# WEMOS_ESP8266_AktorShield.net
KiCad netlist of a schematic drawn in EAGLE
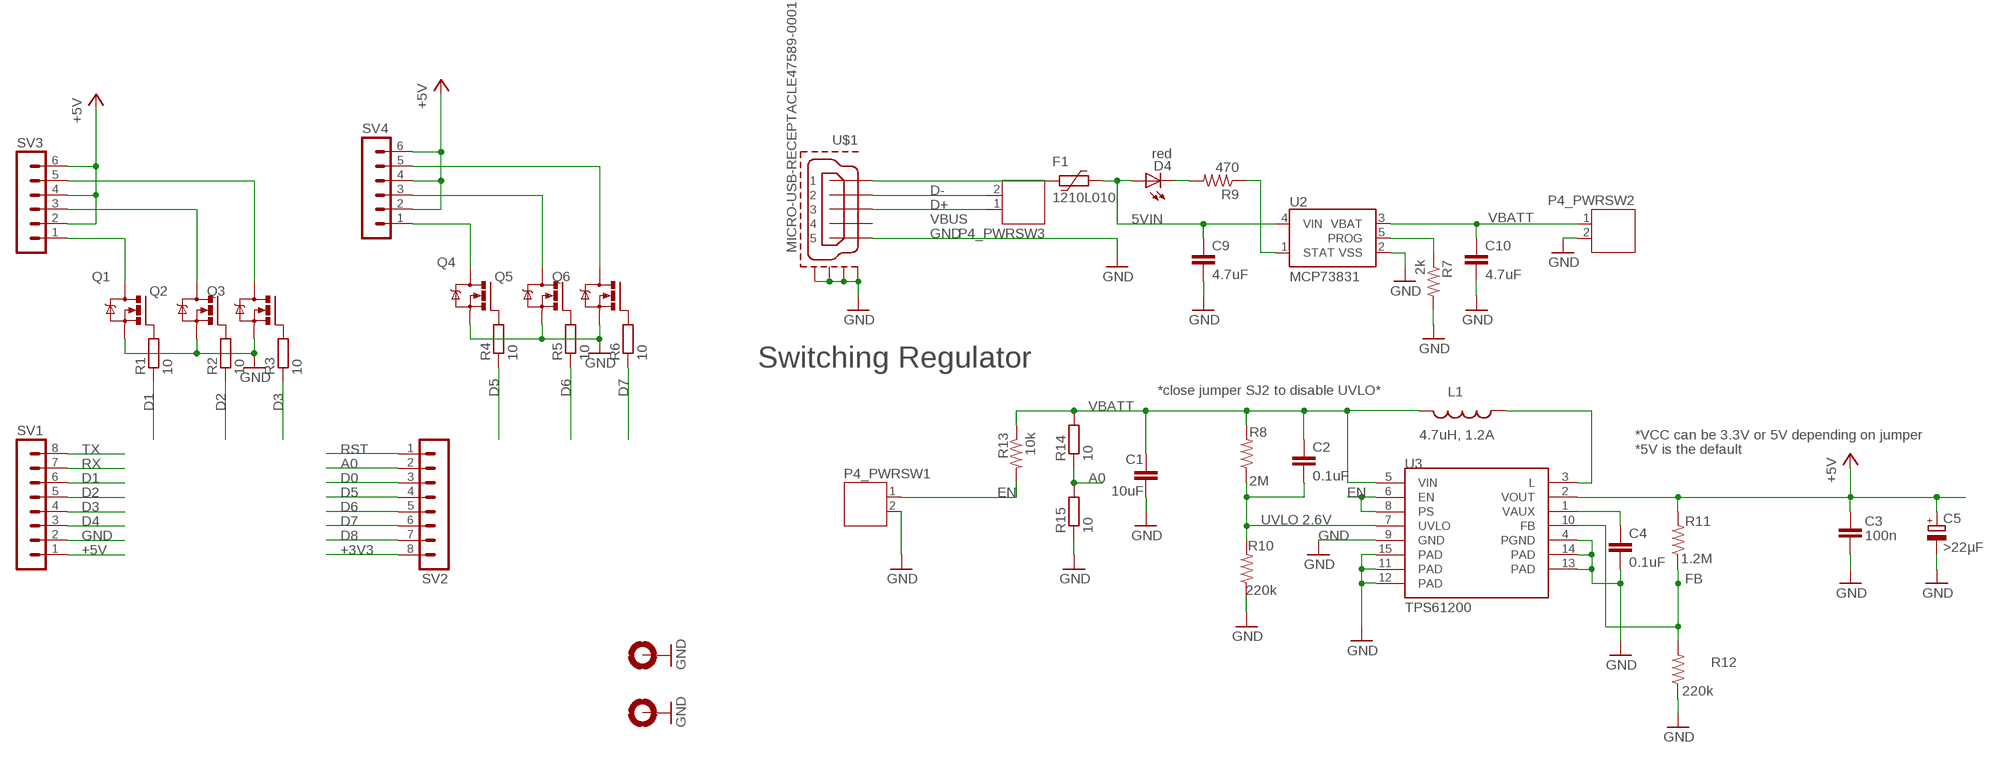
[diagram p0: schematic, sheet 1]

(export (version "E")
  (design (tool "Eeschema 10.0.6"))
  (components
    (comp (ref "C1")
      (value "10uF")
      (footprint "eagle-import:1206")
      (fields (field (name "MF") "KEMET") (field (name "MPN") "C1206C106K8RACTU"))
      (libsource (lib "eagle-import") (part "CAP1206"))
    )
    (comp (ref "C2")
      (value "0.1uF")
      (footprint "eagle-import:0603-CAP")
      (fields (field (name "MF") "YAGEO (PHYCOMP)") (field (name "MPN") "CC0603MRY5V9BB104"))
      (libsource (lib "eagle-import") (part "CAP0603-CAP"))
    )
    (comp (ref "C3")
      (value "100n")
      (footprint "eagle-import:0805")
      (fields (field (name "MF") "YAGEO (PHYCOMP)") (field (name "MPN") "CC0603MRY5V9BB104"))
      (libsource (lib "eagle-import") (part "CAP0805"))
    )
    (comp (ref "C4")
      (value "0.1uF")
      (footprint "eagle-import:0603-CAP")
      (fields (field (name "MF") "YAGEO (PHYCOMP)") (field (name "MPN") "CC0603MRY5V9BB104"))
      (libsource (lib "eagle-import") (part "CAP0603-CAP"))
    )
    (comp (ref "C5")
      (value ">22µF")
      (footprint "eagle-import:SMC_C")
      (libsource (lib "eagle-import") (part "CPOL-EUSMCC"))
    )
    (comp (ref "C9")
      (value "4.7uF")
      (footprint "eagle-import:0603-CAP")
      (fields (field (name "MF") "KEMET") (field (name "MPN") "C0603C475K8PACTU"))
      (libsource (lib "eagle-import") (part "CAP0603-CAP"))
    )
    (comp (ref "C10")
      (value "4.7uF")
      (footprint "eagle-import:0603-CAP")
      (fields (field (name "MF") "KEMET") (field (name "MPN") "C0603C475K8PACTU"))
      (libsource (lib "eagle-import") (part "CAP0603-CAP"))
    )
    (comp (ref "D4")
      (value "red")
      (footprint "eagle-import:LED-0603")
      (fields (field (name "MF") "OSRAM") (field (name "MPN") "LSQ976-Z"))
      (libsource (lib "eagle-import") (part "LED0603"))
    )
    (comp (ref "F1")
      (value "1210L010")
      (footprint "eagle-import:1210L")
      (fields
        (field (name "MF") "Littelfuse")
        (field (name "MF_1") "LITTELFUSE")
        (field (name "MPN") "1210L010WR")
      )
      (libsource (lib "eagle-import") (part "?1210L010"))
    )
    (comp (ref "H7")
      (value "MOUNT-PAD-ROUND3.6")
      (footprint "eagle-import:3,6-PAD")
      (libsource (lib "eagle-import") (part "MOUNT-PAD-ROUND3.6"))
    )
    (comp (ref "H8")
      (value "MOUNT-PAD-ROUND3.6")
      (footprint "eagle-import:3,6-PAD")
      (libsource (lib "eagle-import") (part "MOUNT-PAD-ROUND3.6"))
    )
    (comp (ref "L1")
      (value "4.7uH, 1.2A")
      (footprint "eagle-import:CDRH2D09")
      (fields (field (name "MF") "MURATA") (field (name "MPN") "LQH3NPN4R7MJ0L"))
      (libsource (lib "eagle-import") (part "INDUCTOR."))
    )
    (comp (ref "P4_PWRSW1")
      (value "JST-PH2")
      (footprint "eagle-import:JST-PH2")
      (fields
        (field (name "MF") "JST (JAPAN SOLDERLESS TERMINALS)")
        (field (name "MPN") "B2B-PH-K-S(LF)(SN)")
      )
      (libsource (lib "eagle-import") (part "JST-PH2"))
    )
    (comp (ref "P4_PWRSW2")
      (value "JST-PH2")
      (footprint "eagle-import:JST-PH2")
      (fields
        (field (name "MF") "JST (JAPAN SOLDERLESS TERMINALS)")
        (field (name "MPN") "B2B-PH-K-S(LF)(SN)")
      )
      (libsource (lib "eagle-import") (part "JST-PH2"))
    )
    (comp (ref "P4_PWRSW3")
      (value "JST-PH2")
      (footprint "eagle-import:JST-PH2")
      (fields
        (field (name "MF") "JST (JAPAN SOLDERLESS TERMINALS)")
        (field (name "MPN") "B2B-PH-K-S(LF)(SN)")
      )
      (libsource (lib "eagle-import") (part "JST-PH2"))
    )
    (comp (ref "Q1")
      (value "IRLML6344")
      (footprint "eagle-import:SOT23")
      (fields (field (name "MF") "INFINEON") (field (name "MPN") "IRLML6344TRPBF"))
      (libsource (lib "eagle-import") (part "IRLML6344"))
    )
    (comp (ref "Q2")
      (value "IRLML6344")
      (footprint "eagle-import:SOT23")
      (fields (field (name "MF") "INFINEON") (field (name "MPN") "IRLML6344TRPBF"))
      (libsource (lib "eagle-import") (part "IRLML6344"))
    )
    (comp (ref "Q3")
      (value "IRLML6344")
      (footprint "eagle-import:SOT23")
      (fields (field (name "MF") "INFINEON") (field (name "MPN") "IRLML6344TRPBF"))
      (libsource (lib "eagle-import") (part "IRLML6344"))
    )
    (comp (ref "Q4")
      (value "IRLML6344")
      (footprint "eagle-import:SOT23")
      (fields (field (name "MF") "INFINEON") (field (name "MPN") "IRLML6344TRPBF"))
      (libsource (lib "eagle-import") (part "IRLML6344"))
    )
    (comp (ref "Q5")
      (value "IRLML6344")
      (footprint "eagle-import:SOT23")
      (fields (field (name "MF") "INFINEON") (field (name "MPN") "IRLML6344TRPBF"))
      (libsource (lib "eagle-import") (part "IRLML6344"))
    )
    (comp (ref "Q6")
      (value "IRLML6344")
      (footprint "eagle-import:SOT23")
      (fields (field (name "MF") "INFINEON") (field (name "MPN") "IRLML6344TRPBF"))
      (libsource (lib "eagle-import") (part "IRLML6344"))
    )
    (comp (ref "R1")
      (value "10")
      (footprint "eagle-import:R0603")
      (fields (field (name "MF") "VISHAY") (field (name "MPN") "CRCW060310R0FKEA"))
      (libsource (lib "eagle-import") (part "R-EU_R0603"))
    )
    (comp (ref "R2")
      (value "10")
      (footprint "eagle-import:R0603")
      (fields (field (name "MF") "VISHAY") (field (name "MPN") "CRCW060310R0FKEA"))
      (libsource (lib "eagle-import") (part "R-EU_R0603"))
    )
    (comp (ref "R3")
      (value "10")
      (footprint "eagle-import:R0603")
      (fields (field (name "MF") "VISHAY") (field (name "MPN") "CRCW060310R0FKEA"))
      (libsource (lib "eagle-import") (part "R-EU_R0603"))
    )
    (comp (ref "R4")
      (value "10")
      (footprint "eagle-import:R0603")
      (fields (field (name "MF") "VISHAY") (field (name "MPN") "CRCW060310R0FKEA"))
      (libsource (lib "eagle-import") (part "R-EU_R0603"))
    )
    (comp (ref "R5")
      (value "10")
      (footprint "eagle-import:R0603")
      (fields (field (name "MF") "VISHAY") (field (name "MPN") "CRCW060310R0FKEA"))
      (libsource (lib "eagle-import") (part "R-EU_R0603"))
    )
    (comp (ref "R6")
      (value "10")
      (footprint "eagle-import:R0603")
      (fields (field (name "MF") "VISHAY") (field (name "MPN") "CRCW060310R0FKEA"))
      (libsource (lib "eagle-import") (part "R-EU_R0603"))
    )
    (comp (ref "R7")
      (value "2k")
      (footprint "eagle-import:0603-RES")
      (fields (field (name "MF") "YAGEO (PHYCOMP)") (field (name "MPN") "RC0603FR-072K2L."))
      (libsource (lib "eagle-import") (part "RESISTOR0603-RES"))
    )
    (comp (ref "R8")
      (value "2M")
      (footprint "eagle-import:0603-RES")
      (fields (field (name "MF") "KOA SPEER ELECTRONICS") (field (name "MPN") "RK73H1JTTD1204F"))
      (libsource (lib "eagle-import") (part "RESISTOR0603-RES"))
    )
    (comp (ref "R9")
      (value "470")
      (footprint "eagle-import:0603-RES")
      (fields (field (name "MF") "MULTICOMP") (field (name "MPN") "MCHP03W8F4700T5E"))
      (libsource (lib "eagle-import") (part "RESISTOR0603-RES"))
    )
    (comp (ref "R10")
      (value "220k")
      (footprint "eagle-import:0603-RES")
      (fields (field (name "MF") "MULTICOMP") (field (name "MPN") "MCHP03W8F2203T5E"))
      (libsource (lib "eagle-import") (part "RESISTOR0603-RES"))
    )
    (comp (ref "R11")
      (value "1.2M")
      (footprint "eagle-import:0603-RES")
      (fields (field (name "MF") "MULTICOMP") (field (name "MPN") "MCMR06W2004FTL"))
      (libsource (lib "eagle-import") (part "RESISTOR0603-RES"))
    )
    (comp (ref "R12")
      (value "220k")
      (footprint "eagle-import:0603-RES")
      (fields (field (name "MF") "MULTICOMP") (field (name "MPN") "MCHP03W8F2203T5E"))
      (libsource (lib "eagle-import") (part "RESISTOR0603-RES"))
    )
    (comp (ref "R13")
      (value "10k")
      (footprint "eagle-import:0603-RES")
      (fields (field (name "MF") "MULTICOMP") (field (name "MPN") "MCMR06X1002FTL"))
      (libsource (lib "eagle-import") (part "RESISTOR0603-RES"))
    )
    (comp (ref "R14")
      (value "10")
      (footprint "eagle-import:R0603")
      (fields (field (name "MF") "VISHAY") (field (name "MPN") "CRCW060310R0FKEA"))
      (libsource (lib "eagle-import") (part "R-EU_R0603"))
    )
    (comp (ref "R15")
      (value "10")
      (footprint "eagle-import:R0603")
      (fields (field (name "MF") "VISHAY") (field (name "MPN") "CRCW060310R0FKEA"))
      (libsource (lib "eagle-import") (part "R-EU_R0603"))
    )
    (comp (ref "SV1")
      (value "MA08-1SMALL")
      (footprint "eagle-import:MA08-1S")
      (libsource (lib "eagle-import") (part "MA08-1SMALL"))
    )
    (comp (ref "SV2")
      (value "MA08-1SMALL")
      (footprint "eagle-import:MA08-1S")
      (libsource (lib "eagle-import") (part "MA08-1SMALL"))
    )
    (comp (ref "SV3")
      (value "MA06-1")
      (footprint "eagle-import:MA06-1")
      (libsource (lib "eagle-import") (part "MA06-1"))
    )
    (comp (ref "SV4")
      (value "MA06-1")
      (footprint "eagle-import:MA06-1")
      (libsource (lib "eagle-import") (part "MA06-1"))
    )
    (comp (ref "U$1")
      (value "MICRO-USB-RECEPTACLE47589-0001")
      (footprint "eagle-import:47589-0001")
      (fields (field (name "MF") "MOLEX") (field (name "MPN") "47589-0001"))
      (libsource (lib "eagle-import") (part "MICRO-USB-RECEPTACLE47589-0001"))
    )
    (comp (ref "U2")
      (value "MCP73831")
      (footprint "eagle-import:SOT23-5")
      (fields (field (name "MF") "MICROCHIP") (field (name "MPN") "MCP73831T-2ACI/OT"))
      (libsource (lib "eagle-import") (part "MCP73831"))
    )
    (comp (ref "U3")
      (value "TPS61200")
      (footprint "eagle-import:QFN-10_PAD")
      (fields (field (name "MF") "TEXAS INSTRUMENTS") (field (name "MPN") "TPS61200DRCT"))
      (libsource (lib "eagle-import") (part "TPS61200"))
    )
  )
  (nets
    (net (code "1") (name "+5V") (class "Default")
      (node (ref "C3") (pin "1") (pinfunction "1_1") (pintype "passive"))
      (node (ref "C5") (pin "+") (pinfunction "+_+") (pintype "passive"))
      (node (ref "R11") (pin "2") (pinfunction "2_2") (pintype "passive"))
      (node (ref "SV1") (pin "1") (pinfunction "1_1") (pintype "passive"))
      (node (ref "SV3") (pin "2") (pinfunction "2_2") (pintype "passive"))
      (node (ref "SV3") (pin "4") (pinfunction "4_4") (pintype "passive"))
      (node (ref "SV3") (pin "6") (pinfunction "6_6") (pintype "passive"))
      (node (ref "SV4") (pin "2") (pinfunction "2_2") (pintype "passive"))
      (node (ref "SV4") (pin "4") (pinfunction "4_4") (pintype "passive"))
      (node (ref "SV4") (pin "6") (pinfunction "6_6") (pintype "passive"))
      (node (ref "U3") (pin "2") (pinfunction "VOUT_2") (pintype "passive"))
    )
    (net (code "2") (name "/+3V3") (class "Default")
      (node (ref "SV2") (pin "8") (pinfunction "8_8") (pintype "passive"))
    )
    (net (code "3") (name "/5VIN") (class "Default")
      (node (ref "C9") (pin "1") (pinfunction "1_1") (pintype "passive"))
      (node (ref "D4") (pin "A") (pinfunction "A_A") (pintype "passive"))
      (node (ref "F1") (pin "1") (pinfunction "1_1") (pintype "passive"))
      (node (ref "U2") (pin "4") (pinfunction "VIN_4") (pintype "power_in"))
    )
    (net (code "4") (name "/A0") (class "Default")
      (node (ref "R14") (pin "1") (pinfunction "1_1") (pintype "passive"))
      (node (ref "R15") (pin "2") (pinfunction "2_2") (pintype "passive"))
      (node (ref "SV2") (pin "2") (pinfunction "2_2") (pintype "passive"))
    )
    (net (code "5") (name "/D+") (class "Default")
      (node (ref "P4_PWRSW3") (pin "1") (pinfunction "1_1") (pintype "passive"))
      (node (ref "U$1") (pin "3") (pinfunction "3_3") (pintype "input"))
    )
    (net (code "6") (name "/D-") (class "Default")
      (node (ref "P4_PWRSW3") (pin "2") (pinfunction "2_2") (pintype "passive"))
      (node (ref "U$1") (pin "2") (pinfunction "2_2") (pintype "input"))
    )
    (net (code "7") (name "/D0") (class "Default")
      (node (ref "SV2") (pin "3") (pinfunction "3_3") (pintype "passive"))
    )
    (net (code "8") (name "/D1") (class "Default")
      (node (ref "R1") (pin "1") (pinfunction "1_1") (pintype "passive"))
      (node (ref "SV1") (pin "6") (pinfunction "6_6") (pintype "passive"))
    )
    (net (code "9") (name "/D2") (class "Default")
      (node (ref "R2") (pin "1") (pinfunction "1_1") (pintype "passive"))
      (node (ref "SV1") (pin "5") (pinfunction "5_5") (pintype "passive"))
    )
    (net (code "10") (name "/D3") (class "Default")
      (node (ref "R3") (pin "1") (pinfunction "1_1") (pintype "passive"))
      (node (ref "SV1") (pin "4") (pinfunction "4_4") (pintype "passive"))
    )
    (net (code "11") (name "/D4") (class "Default")
      (node (ref "SV1") (pin "3") (pinfunction "3_3") (pintype "passive"))
    )
    (net (code "12") (name "/D5") (class "Default")
      (node (ref "R4") (pin "1") (pinfunction "1_1") (pintype "passive"))
      (node (ref "SV2") (pin "4") (pinfunction "4_4") (pintype "passive"))
    )
    (net (code "13") (name "/D6") (class "Default")
      (node (ref "R5") (pin "1") (pinfunction "1_1") (pintype "passive"))
      (node (ref "SV2") (pin "5") (pinfunction "5_5") (pintype "passive"))
    )
    (net (code "14") (name "/D7") (class "Default")
      (node (ref "R6") (pin "1") (pinfunction "1_1") (pintype "passive"))
      (node (ref "SV2") (pin "6") (pinfunction "6_6") (pintype "passive"))
    )
    (net (code "15") (name "/D8") (class "Default")
      (node (ref "SV2") (pin "7") (pinfunction "7_7") (pintype "passive"))
    )
    (net (code "16") (name "/EN") (class "Default")
      (node (ref "P4_PWRSW1") (pin "1") (pinfunction "1_1") (pintype "passive"))
      (node (ref "R13") (pin "2") (pinfunction "2_2") (pintype "passive"))
      (node (ref "U3") (pin "6") (pinfunction "EN_6") (pintype "input"))
      (node (ref "U3") (pin "8") (pinfunction "PS_8") (pintype "input"))
    )
    (net (code "17") (name "/FB") (class "Default")
      (node (ref "R11") (pin "1") (pinfunction "1_1") (pintype "passive"))
      (node (ref "R12") (pin "2") (pinfunction "2_2") (pintype "passive"))
      (node (ref "U3") (pin "10") (pinfunction "FB_10") (pintype "passive"))
    )
    (net (code "18") (name "/RST") (class "Default")
      (node (ref "SV2") (pin "1") (pinfunction "1_1") (pintype "passive"))
    )
    (net (code "19") (name "/RX") (class "Default")
      (node (ref "SV1") (pin "7") (pinfunction "7_7") (pintype "passive"))
    )
    (net (code "20") (name "/TX") (class "Default")
      (node (ref "SV1") (pin "8") (pinfunction "8_8") (pintype "passive"))
    )
    (net (code "21") (name "/VBATT") (class "Default")
      (node (ref "C1") (pin "1") (pinfunction "1_1") (pintype "passive"))
      (node (ref "C10") (pin "1") (pinfunction "1_1") (pintype "passive"))
      (node (ref "C2") (pin "1") (pinfunction "1_1") (pintype "passive"))
      (node (ref "L1") (pin "P$2") (pinfunction "2_P$2") (pintype "passive"))
      (node (ref "P4_PWRSW2") (pin "1") (pinfunction "1_1") (pintype "passive"))
      (node (ref "R13") (pin "1") (pinfunction "1_1") (pintype "passive"))
      (node (ref "R14") (pin "2") (pinfunction "2_2") (pintype "passive"))
      (node (ref "R8") (pin "2") (pinfunction "2_2") (pintype "passive"))
      (node (ref "U2") (pin "3") (pinfunction "VBAT_3") (pintype "power_in"))
      (node (ref "U3") (pin "5") (pinfunction "VIN_5") (pintype "power_in"))
    )
    (net (code "22") (name "/VBUS") (class "Default")
      (node (ref "F1") (pin "2") (pinfunction "2_2") (pintype "passive"))
      (node (ref "U$1") (pin "1") (pinfunction "1_1") (pintype "input"))
    )
    (net (code "23") (name "GND") (class "Default")
      (node (ref "C1") (pin "2") (pinfunction "2_2") (pintype "passive"))
      (node (ref "C10") (pin "2") (pinfunction "2_2") (pintype "passive"))
      (node (ref "C3") (pin "2") (pinfunction "2_2") (pintype "passive"))
      (node (ref "C4") (pin "2") (pinfunction "2_2") (pintype "passive"))
      (node (ref "C5") (pin "-") (pinfunction "-_-") (pintype "passive"))
      (node (ref "C9") (pin "2") (pinfunction "2_2") (pintype "passive"))
      (node (ref "H7") (pin "B3,6") (pinfunction "MOUNT_B3,6") (pintype "passive"))
      (node (ref "H8") (pin "B3,6") (pinfunction "MOUNT_B3,6") (pintype "passive"))
      (node (ref "P4_PWRSW1") (pin "2") (pinfunction "2_2") (pintype "passive"))
      (node (ref "P4_PWRSW2") (pin "2") (pinfunction "2_2") (pintype "passive"))
      (node (ref "Q1") (pin "2") (pinfunction "S_2") (pintype "passive"))
      (node (ref "Q2") (pin "2") (pinfunction "S_2") (pintype "passive"))
      (node (ref "Q3") (pin "2") (pinfunction "S_2") (pintype "passive"))
      (node (ref "Q4") (pin "2") (pinfunction "S_2") (pintype "passive"))
      (node (ref "Q5") (pin "2") (pinfunction "S_2") (pintype "passive"))
      (node (ref "Q6") (pin "2") (pinfunction "S_2") (pintype "passive"))
      (node (ref "R10") (pin "1") (pinfunction "1_1") (pintype "passive"))
      (node (ref "R12") (pin "1") (pinfunction "1_1") (pintype "passive"))
      (node (ref "R15") (pin "1") (pinfunction "1_1") (pintype "passive"))
      (node (ref "R7") (pin "2") (pinfunction "2_2") (pintype "passive"))
      (node (ref "SV1") (pin "2") (pinfunction "2_2") (pintype "passive"))
      (node (ref "U$1") (pin "5") (pinfunction "5_5") (pintype "input"))
      (node (ref "U$1") (pin "CASING1") (pinfunction "GND1_CASING1") (pintype "bidirectional"))
      (node (ref "U$1") (pin "CASING2") (pinfunction "GND2_CASING2") (pintype "bidirectional"))
      (node (ref "U$1") (pin "CASING3") (pinfunction "GND3_CASING3") (pintype "bidirectional"))
      (node (ref "U$1") (pin "CASING4") (pinfunction "GND4_CASING4") (pintype "bidirectional"))
      (node (ref "U2") (pin "2") (pinfunction "VSS_2") (pintype "power_in"))
      (node (ref "U3") (pin "11") (pinfunction "PAD_11") (pintype "power_in"))
      (node (ref "U3") (pin "12") (pinfunction "PAD_12") (pintype "power_in"))
      (node (ref "U3") (pin "13") (pinfunction "PAD_13") (pintype "power_in"))
      (node (ref "U3") (pin "14") (pinfunction "PAD_14") (pintype "power_in"))
      (node (ref "U3") (pin "15") (pinfunction "PAD_15") (pintype "power_in"))
      (node (ref "U3") (pin "4") (pinfunction "PGND_4") (pintype "power_in"))
      (node (ref "U3") (pin "9") (pinfunction "GND_9") (pintype "power_in"))
    )
    (net (code "24") (name "Net-(D4-PadC)") (class "Default")
      (node (ref "D4") (pin "C") (pinfunction "C_C") (pintype "passive"))
      (node (ref "R9") (pin "2") (pinfunction "2_2") (pintype "passive"))
    )
    (net (code "25") (name "Net-(L1-1)") (class "Default")
      (node (ref "L1") (pin "P$1") (pinfunction "1_P$1") (pintype "passive"))
      (node (ref "U3") (pin "3") (pinfunction "L_3") (pintype "passive"))
    )
    (net (code "26") (name "Net-(Q1-D)") (class "Default")
      (node (ref "Q1") (pin "3") (pinfunction "D_3") (pintype "passive"))
      (node (ref "SV3") (pin "1") (pinfunction "1_1") (pintype "passive"))
    )
    (net (code "27") (name "Net-(Q1-G)") (class "Default")
      (node (ref "Q1") (pin "1") (pinfunction "G_1") (pintype "passive"))
      (node (ref "R1") (pin "2") (pinfunction "2_2") (pintype "passive"))
    )
    (net (code "28") (name "Net-(Q2-D)") (class "Default")
      (node (ref "Q2") (pin "3") (pinfunction "D_3") (pintype "passive"))
      (node (ref "SV3") (pin "3") (pinfunction "3_3") (pintype "passive"))
    )
    (net (code "29") (name "Net-(Q2-G)") (class "Default")
      (node (ref "Q2") (pin "1") (pinfunction "G_1") (pintype "passive"))
      (node (ref "R2") (pin "2") (pinfunction "2_2") (pintype "passive"))
    )
    (net (code "30") (name "Net-(Q3-D)") (class "Default")
      (node (ref "Q3") (pin "3") (pinfunction "D_3") (pintype "passive"))
      (node (ref "SV3") (pin "5") (pinfunction "5_5") (pintype "passive"))
    )
    (net (code "31") (name "Net-(Q3-G)") (class "Default")
      (node (ref "Q3") (pin "1") (pinfunction "G_1") (pintype "passive"))
      (node (ref "R3") (pin "2") (pinfunction "2_2") (pintype "passive"))
    )
    (net (code "32") (name "Net-(Q4-D)") (class "Default")
      (node (ref "Q4") (pin "3") (pinfunction "D_3") (pintype "passive"))
      (node (ref "SV4") (pin "1") (pinfunction "1_1") (pintype "passive"))
    )
    (net (code "33") (name "Net-(Q4-G)") (class "Default")
      (node (ref "Q4") (pin "1") (pinfunction "G_1") (pintype "passive"))
      (node (ref "R4") (pin "2") (pinfunction "2_2") (pintype "passive"))
    )
    (net (code "34") (name "Net-(Q5-D)") (class "Default")
      (node (ref "Q5") (pin "3") (pinfunction "D_3") (pintype "passive"))
      (node (ref "SV4") (pin "3") (pinfunction "3_3") (pintype "passive"))
    )
    (net (code "35") (name "Net-(Q5-G)") (class "Default")
      (node (ref "Q5") (pin "1") (pinfunction "G_1") (pintype "passive"))
      (node (ref "R5") (pin "2") (pinfunction "2_2") (pintype "passive"))
    )
    (net (code "36") (name "Net-(Q6-D)") (class "Default")
      (node (ref "Q6") (pin "3") (pinfunction "D_3") (pintype "passive"))
      (node (ref "SV4") (pin "5") (pinfunction "5_5") (pintype "passive"))
    )
    (net (code "37") (name "Net-(Q6-G)") (class "Default")
      (node (ref "Q6") (pin "1") (pinfunction "G_1") (pintype "passive"))
      (node (ref "R6") (pin "2") (pinfunction "2_2") (pintype "passive"))
    )
    (net (code "38") (name "Net-(U2-PROG)") (class "Default")
      (node (ref "R7") (pin "1") (pinfunction "1_1") (pintype "passive"))
      (node (ref "U2") (pin "5") (pinfunction "PROG_5") (pintype "input"))
    )
    (net (code "39") (name "Net-(U2-STAT)") (class "Default")
      (node (ref "R9") (pin "1") (pinfunction "1_1") (pintype "passive"))
      (node (ref "U2") (pin "1") (pinfunction "STAT_1") (pintype "output"))
    )
    (net (code "40") (name "Net-(U3-UVLO)") (class "Default")
      (node (ref "C2") (pin "2") (pinfunction "2_2") (pintype "passive"))
      (node (ref "R10") (pin "2") (pinfunction "2_2") (pintype "passive"))
      (node (ref "R8") (pin "1") (pinfunction "1_1") (pintype "passive"))
      (node (ref "U3") (pin "7") (pinfunction "UVLO_7") (pintype "passive"))
    )
    (net (code "41") (name "Net-(U3-VAUX)") (class "Default")
      (node (ref "C4") (pin "1") (pinfunction "1_1") (pintype "passive"))
      (node (ref "U3") (pin "1") (pinfunction "VAUX_1") (pintype "passive"))
    )
    (net (code "42") (name "unconnected-(U$1-Pad4)") (class "Default")
      (node (ref "U$1") (pin "4") (pinfunction "4_4") (pintype "input"))
    )
  )
)
